# cmos-guy.net
KiCad netlist of a schematic drawn in EAGLE
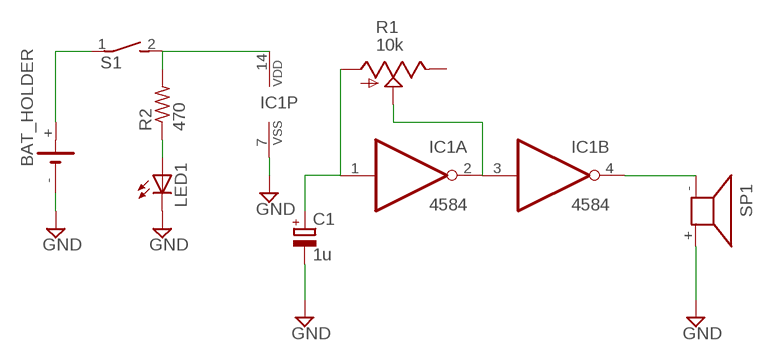
[diagram p0: schematic, sheet 1]

(export (version "E")
  (design (tool "Eeschema 10.0.6"))
  (components
    (comp (ref "BAT_HOLDER")
      (value "CH291-1220LF")
      (footprint "eagle-import:CH291-1220LF")
      (libsource (lib "eagle-import") (part "CH291-1220LF"))
    )
    (comp (ref "C1")
      (value "1u")
      (footprint "eagle-import:E2,5-5")
      (libsource (lib "eagle-import") (part "CPOL-EUE2.5-5"))
    )
    (comp (ref "IC1")
      (value "4584")
      (footprint "eagle-import:DIL14")
      (libsource (lib "eagle-import") (part "4584N"))
    )
    (comp (ref "LED1")
      (value "LBP4-BOTTOM")
      (footprint "eagle-import:P47F-BOTTOM")
      (libsource (lib "eagle-import") (part "P4-BOTTOMLB"))
    )
    (comp (ref "R1")
      (value "10k")
      (footprint "eagle-import:RJ6S")
      (libsource (lib "eagle-import") (part "TRIM_US-RJ6S"))
    )
    (comp (ref "R2")
      (value "470")
      (footprint "eagle-import:0204_5")
      (libsource (lib "eagle-import") (part "R-US_0204/5"))
    )
    (comp (ref "S1")
      (value "DS01E")
      (footprint "eagle-import:DS-01")
      (libsource (lib "eagle-import") (part "DS01E"))
    )
    (comp (ref "SP1")
      (value "AL11P")
      (footprint "eagle-import:AL11P")
      (libsource (lib "eagle-import") (part "AL11P"))
    )
  )
  (nets
    (net (code "1") (name "GND") (class "Default")
      (node (ref "BAT_HOLDER") (pin "-") (pinfunction "-_-") (pintype "passive"))
      (node (ref "C1") (pin "-") (pinfunction "-_-") (pintype "passive"))
      (node (ref "IC1") (pin "7") (pinfunction "VSS_7") (pintype "power_in"))
      (node (ref "LED1") (pin "C") (pinfunction "C_C") (pintype "passive"))
      (node (ref "SP1") (pin "+") (pinfunction "2_+") (pintype "passive"))
    )
    (net (code "2") (name "Net-(BAT_HOLDER-Pad+)") (class "Default")
      (node (ref "BAT_HOLDER") (pin "+") (pinfunction "+_+") (pintype "passive"))
      (node (ref "S1") (pin "1") (pinfunction "1_1") (pintype "passive"))
    )
    (net (code "3") (name "Net-(IC1A-I)") (class "Default")
      (node (ref "C1") (pin "+") (pinfunction "+_+") (pintype "passive"))
      (node (ref "IC1") (pin "1") (pinfunction "I_1") (pintype "input"))
      (node (ref "R1") (pin "A") (pinfunction "A_A") (pintype "passive"))
    )
    (net (code "4") (name "Net-(IC1A-O)") (class "Default")
      (node (ref "IC1") (pin "2") (pinfunction "O_2") (pintype "output"))
      (node (ref "IC1") (pin "3") (pinfunction "I_3") (pintype "input"))
      (node (ref "R1") (pin "S") (pinfunction "S_S") (pintype "passive"))
    )
    (net (code "5") (name "Net-(IC1B-O)") (class "Default")
      (node (ref "IC1") (pin "4") (pinfunction "O_4") (pintype "output"))
      (node (ref "SP1") (pin "-") (pinfunction "1_-") (pintype "passive"))
    )
    (net (code "6") (name "Net-(IC1G-VDD)") (class "Default")
      (node (ref "IC1") (pin "14") (pinfunction "VDD_14") (pintype "power_in"))
      (node (ref "R2") (pin "2") (pinfunction "2_2") (pintype "passive"))
      (node (ref "S1") (pin "2") (pinfunction "2_2") (pintype "passive"))
    )
    (net (code "7") (name "Net-(LED1-PadA)") (class "Default")
      (node (ref "LED1") (pin "A") (pinfunction "A_A") (pintype "passive"))
      (node (ref "R2") (pin "1") (pinfunction "1_1") (pintype "passive"))
    )
    (net (code "8") (name "unconnected-(R1-PadE)") (class "Default")
      (node (ref "R1") (pin "E") (pinfunction "E_E") (pintype "passive"))
    )
  )
)
